# TxFM.net
KiCad netlist of a schematic drawn in Altium Designer
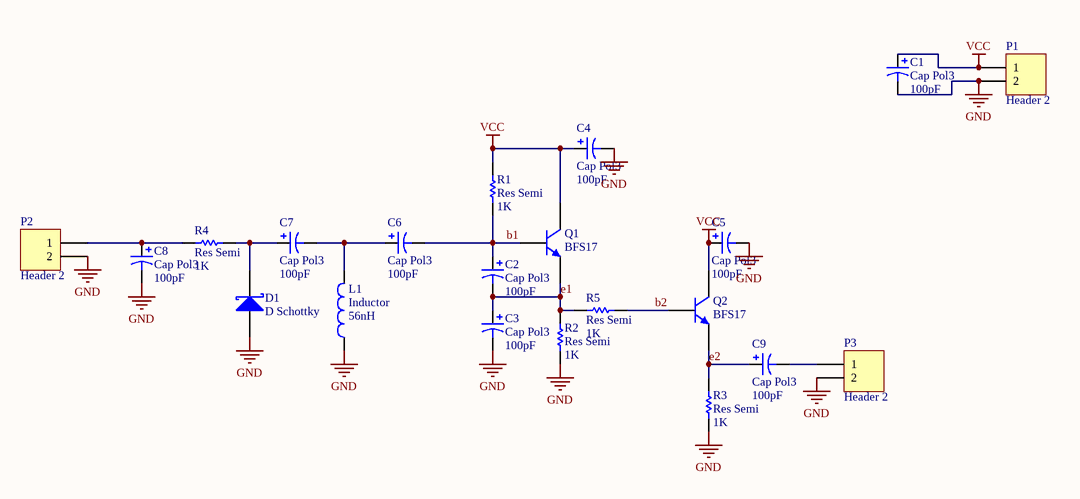
[diagram p0: TxFM.SchDoc]

(export (version "E")
  (design (tool "Eeschema 10.0.6"))
  (components
    (comp (ref "C1")
      (value "Cap Pol3")
      (footprint "C0805")
      (description "Polarized Capacitor (Surface Mount)")
      (fields (field (name "ALTIUM_VALUE") "100pF") (field (name "PUBLISHER") "Altium Limited"))
      (libsource (lib "Miscellaneous Devices") (part "Cap Pol3"))
    )
    (comp (ref "C2")
      (value "Cap Pol3")
      (footprint "C0805")
      (description "Polarized Capacitor (Surface Mount)")
      (fields (field (name "ALTIUM_VALUE") "100pF") (field (name "PUBLISHER") "Altium Limited"))
      (libsource (lib "Miscellaneous Devices") (part "Cap Pol3"))
    )
    (comp (ref "C3")
      (value "Cap Pol3")
      (footprint "C0805")
      (description "Polarized Capacitor (Surface Mount)")
      (fields (field (name "ALTIUM_VALUE") "100pF") (field (name "PUBLISHER") "Altium Limited"))
      (libsource (lib "Miscellaneous Devices") (part "Cap Pol3"))
    )
    (comp (ref "C4")
      (value "Cap Pol3")
      (footprint "C0805")
      (description "Polarized Capacitor (Surface Mount)")
      (fields (field (name "ALTIUM_VALUE") "100pF") (field (name "PUBLISHER") "Altium Limited"))
      (libsource (lib "Miscellaneous Devices") (part "Cap Pol3"))
    )
    (comp (ref "C5")
      (value "Cap Pol3")
      (footprint "C0805")
      (description "Polarized Capacitor (Surface Mount)")
      (fields (field (name "ALTIUM_VALUE") "100pF") (field (name "PUBLISHER") "Altium Limited"))
      (libsource (lib "Miscellaneous Devices") (part "Cap Pol3"))
    )
    (comp (ref "C6")
      (value "Cap Pol3")
      (footprint "C0805")
      (description "Polarized Capacitor (Surface Mount)")
      (fields (field (name "ALTIUM_VALUE") "100pF") (field (name "PUBLISHER") "Altium Limited"))
      (libsource (lib "Miscellaneous Devices") (part "Cap Pol3"))
    )
    (comp (ref "C7")
      (value "Cap Pol3")
      (footprint "C0805")
      (description "Polarized Capacitor (Surface Mount)")
      (fields (field (name "ALTIUM_VALUE") "100pF") (field (name "PUBLISHER") "Altium Limited"))
      (libsource (lib "Miscellaneous Devices") (part "Cap Pol3"))
    )
    (comp (ref "C8")
      (value "Cap Pol3")
      (footprint "C0805")
      (description "Polarized Capacitor (Surface Mount)")
      (fields (field (name "ALTIUM_VALUE") "100pF") (field (name "PUBLISHER") "Altium Limited"))
      (libsource (lib "Miscellaneous Devices") (part "Cap Pol3"))
    )
    (comp (ref "C9")
      (value "Cap Pol3")
      (footprint "C0805")
      (description "Polarized Capacitor (Surface Mount)")
      (fields (field (name "ALTIUM_VALUE") "100pF") (field (name "PUBLISHER") "Altium Limited"))
      (libsource (lib "Miscellaneous Devices") (part "Cap Pol3"))
    )
    (comp (ref "D1")
      (value "D Schottky")
      (footprint "SMB")
      (description "Schottky Diode")
      (fields (field (name "PUBLISHER") "Altium Limited"))
      (libsource (lib "Miscellaneous Devices") (part "D Schottky"))
    )
    (comp (ref "L1")
      (value "Inductor")
      (footprint "0402-A")
      (fields (field (name "ALTIUM_VALUE") "56nH") (field (name "PUBLISHER") "Altium Limited"))
      (libsource (lib "Miscellaneous Devices") (part "Inductor"))
    )
    (comp (ref "P1")
      (value "Header 2")
      (footprint "HDR1X2")
      (description "Header, 2-Pin")
      (fields (field (name "PUBLISHER") "Altium Limited"))
      (libsource (lib "Miscellaneous Connectors") (part "Header 2"))
    )
    (comp (ref "P2")
      (value "Header 2")
      (footprint "HDR1X2")
      (description "Header, 2-Pin")
      (fields (field (name "PUBLISHER") "Altium Limited"))
      (libsource (lib "") (part "Header 2_1"))
    )
    (comp (ref "P3")
      (value "Header 2")
      (footprint "HDR1X2")
      (description "Header, 2-Pin")
      (fields (field (name "PUBLISHER") "Altium Limited"))
      (libsource (lib "Miscellaneous Connectors") (part "Header 2"))
    )
    (comp (ref "Q1")
      (value "BFS17")
      (footprint "SOT23")
      (description "NPN 1 GHz Wideband Transistor")
      (fields (field (name "PUBLISHER") "Altium Limited"))
      (libsource (lib "Philips Discrete BJT - RF Transistor") (part "BFS17"))
    )
    (comp (ref "Q2")
      (value "BFS17")
      (footprint "SOT23")
      (description "NPN 1 GHz Wideband Transistor")
      (fields (field (name "PUBLISHER") "Altium Limited"))
      (libsource (lib "Philips Discrete BJT - RF Transistor") (part "BFS17"))
    )
    (comp (ref "R1")
      (value "Res Semi")
      (footprint "2012[0805]")
      (description "Semiconductor Resistor")
      (fields (field (name "ALTIUM_VALUE") "1K") (field (name "PUBLISHER") "Altium Limited"))
      (libsource (lib "Miscellaneous Devices") (part "Res Semi"))
    )
    (comp (ref "R2")
      (value "Res Semi")
      (footprint "2012[0805]")
      (description "Semiconductor Resistor")
      (fields (field (name "ALTIUM_VALUE") "1K") (field (name "PUBLISHER") "Altium Limited"))
      (libsource (lib "Miscellaneous Devices") (part "Res Semi"))
    )
    (comp (ref "R3")
      (value "Res Semi")
      (footprint "2012[0805]")
      (description "Semiconductor Resistor")
      (fields (field (name "ALTIUM_VALUE") "1K") (field (name "PUBLISHER") "Altium Limited"))
      (libsource (lib "Miscellaneous Devices") (part "Res Semi"))
    )
    (comp (ref "R4")
      (value "Res Semi")
      (footprint "2012[0805]")
      (description "Semiconductor Resistor")
      (fields (field (name "ALTIUM_VALUE") "1K") (field (name "PUBLISHER") "Altium Limited"))
      (libsource (lib "Miscellaneous Devices") (part "Res Semi"))
    )
    (comp (ref "R5")
      (value "Res Semi")
      (footprint "2012[0805]")
      (description "Semiconductor Resistor")
      (fields (field (name "ALTIUM_VALUE") "1K") (field (name "PUBLISHER") "Altium Limited"))
      (libsource (lib "Miscellaneous Devices") (part "Res Semi"))
    )
  )
  (nets
    (net (code "1") (name "/b1") (class "Default")
      (node (ref "C2") (pin "1") (pinfunction "1_1") (pintype "passive"))
      (node (ref "C6") (pin "2") (pinfunction "2_2") (pintype "passive"))
      (node (ref "Q1") (pin "1") (pinfunction "B_1") (pintype "passive"))
      (node (ref "R1") (pin "1") (pinfunction "1_1") (pintype "passive"))
    )
    (net (code "2") (name "/b2") (class "Default")
      (node (ref "Q2") (pin "1") (pinfunction "B_1") (pintype "passive"))
      (node (ref "R5") (pin "1") (pinfunction "1_1") (pintype "passive"))
    )
    (net (code "3") (name "/e1") (class "Default")
      (node (ref "C2") (pin "2") (pinfunction "2_2") (pintype "passive"))
      (node (ref "C3") (pin "1") (pinfunction "1_1") (pintype "passive"))
      (node (ref "Q1") (pin "2") (pinfunction "E_2") (pintype "passive"))
      (node (ref "R2") (pin "2") (pinfunction "2_2") (pintype "passive"))
      (node (ref "R5") (pin "2") (pinfunction "2_2") (pintype "passive"))
    )
    (net (code "4") (name "/e2") (class "Default")
      (node (ref "C9") (pin "1") (pinfunction "1_1") (pintype "passive"))
      (node (ref "Q2") (pin "2") (pinfunction "E_2") (pintype "passive"))
      (node (ref "R3") (pin "2") (pinfunction "2_2") (pintype "passive"))
    )
    (net (code "5") (name "GND") (class "Default")
      (node (ref "C1") (pin "2") (pinfunction "2_2") (pintype "passive"))
      (node (ref "C3") (pin "2") (pinfunction "2_2") (pintype "passive"))
      (node (ref "C4") (pin "2") (pinfunction "2_2") (pintype "passive"))
      (node (ref "C5") (pin "2") (pinfunction "2_2") (pintype "passive"))
      (node (ref "C8") (pin "2") (pinfunction "2_2") (pintype "passive"))
      (node (ref "D1") (pin "1") (pinfunction "A_1") (pintype "passive"))
      (node (ref "L1") (pin "1") (pinfunction "1_1") (pintype "passive"))
      (node (ref "P1") (pin "2") (pinfunction "2_2") (pintype "passive"))
      (node (ref "P2") (pin "2") (pinfunction "2_2") (pintype "passive"))
      (node (ref "P3") (pin "2") (pinfunction "2_2") (pintype "passive"))
      (node (ref "R2") (pin "1") (pinfunction "1_1") (pintype "passive"))
      (node (ref "R3") (pin "1") (pinfunction "1_1") (pintype "passive"))
    )
    (net (code "6") (name "Net-(C6-Pad1)") (class "Default")
      (node (ref "C6") (pin "1") (pinfunction "1_1") (pintype "passive"))
      (node (ref "C7") (pin "2") (pinfunction "2_2") (pintype "passive"))
      (node (ref "L1") (pin "2") (pinfunction "2_2") (pintype "passive"))
    )
    (net (code "7") (name "Net-(C8-Pad1)") (class "Default")
      (node (ref "C8") (pin "1") (pinfunction "1_1") (pintype "passive"))
      (node (ref "P2") (pin "1") (pinfunction "1_1") (pintype "passive"))
      (node (ref "R4") (pin "2") (pinfunction "2_2") (pintype "passive"))
    )
    (net (code "8") (name "Net-(C9-Pad2)") (class "Default")
      (node (ref "C9") (pin "2") (pinfunction "2_2") (pintype "passive"))
      (node (ref "P3") (pin "1") (pinfunction "1_1") (pintype "passive"))
    )
    (net (code "9") (name "Net-(D1-K)") (class "Default")
      (node (ref "C7") (pin "1") (pinfunction "1_1") (pintype "passive"))
      (node (ref "D1") (pin "2") (pinfunction "K_2") (pintype "passive"))
      (node (ref "R4") (pin "1") (pinfunction "1_1") (pintype "passive"))
    )
    (net (code "10") (name "VCC") (class "Default")
      (node (ref "C1") (pin "1") (pinfunction "1_1") (pintype "passive"))
      (node (ref "C4") (pin "1") (pinfunction "1_1") (pintype "passive"))
      (node (ref "C5") (pin "1") (pinfunction "1_1") (pintype "passive"))
      (node (ref "P1") (pin "1") (pinfunction "1_1") (pintype "passive"))
      (node (ref "Q1") (pin "3") (pinfunction "C_3") (pintype "passive"))
      (node (ref "Q2") (pin "3") (pinfunction "C_3") (pintype "passive"))
      (node (ref "R1") (pin "2") (pinfunction "2_2") (pintype "passive"))
    )
  )
)
